# Sheet1.net
KiCad netlist of a schematic drawn in Altium Designer
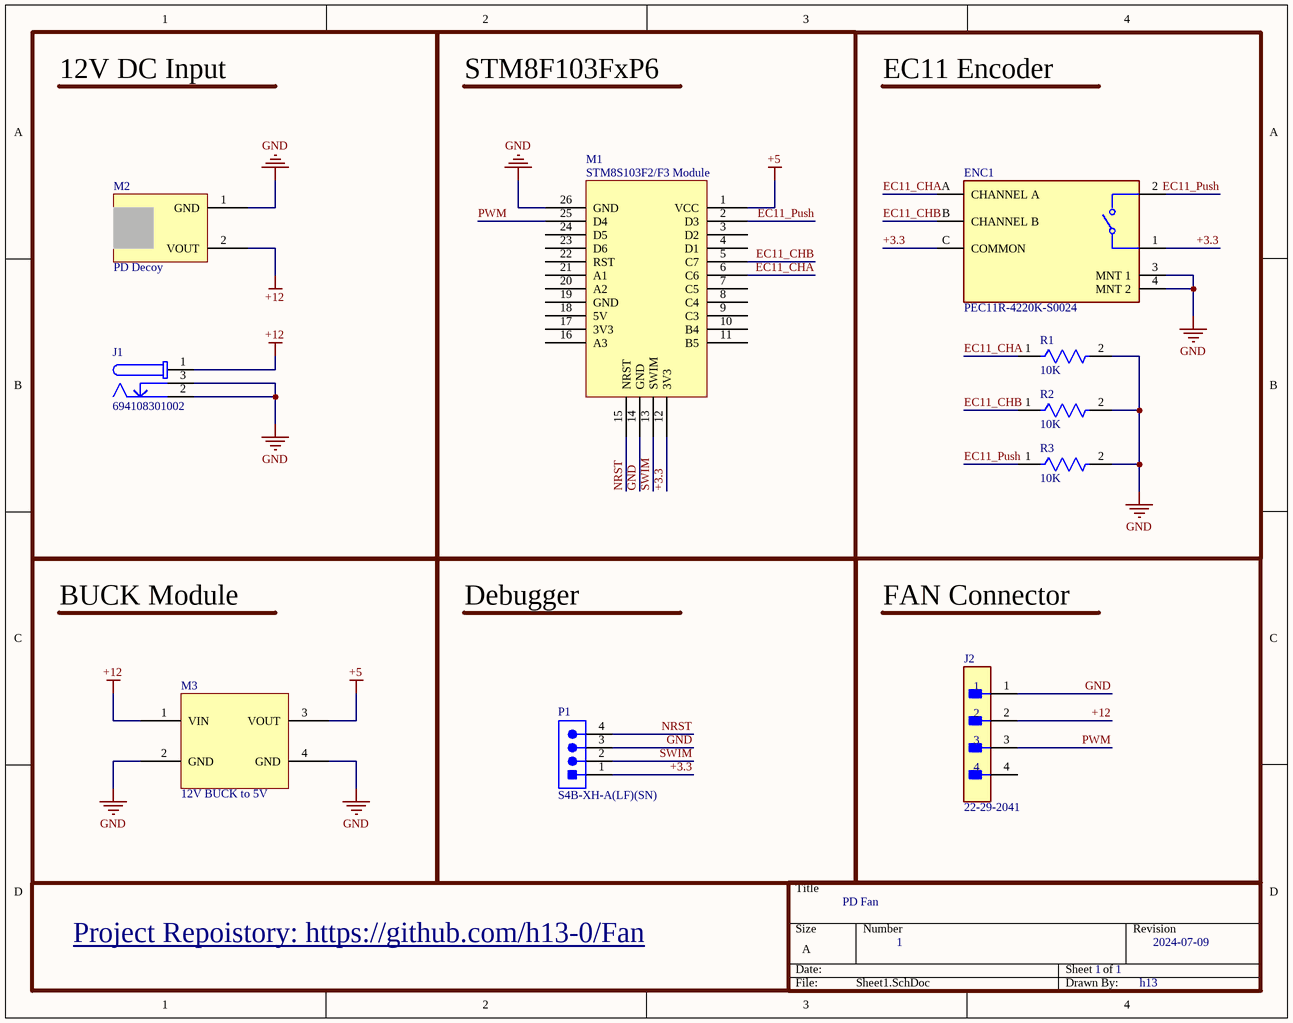
[diagram p0: Sheet1.SchDoc]

(export (version "E")
  (design (tool "Eeschema 10.0.6"))
  (components
    (comp (ref "ENC1")
      (value "PEC11R-4220K-S0024")
      (footprint "FP-PEC11R-4220K-S0024-MFG")
      (description "ROTARY ENCODER INCREMENTAL 24PPR")
      (libsource (lib "Altium Content Vault") (part "d75f9e24c474ed3fe2cf82f27e06f2a"))
    )
    (comp (ref "J1")
      (value "694108301002")
      (footprint "694108301002")
      (libsource (lib "Altium Content Vault") (part "DC Power Jack"))
    )
    (comp (ref "J2")
      (value "22-29-2041")
      (footprint "FP-22-29-2041-MFG")
      (description "CONN HEADER VERT 4POS 2.54MM")
      (libsource (lib "Altium Content Vault") (part "299a8cea1bdcbc3624fe62c390fa72c"))
    )
    (comp (ref "M1")
      (value "STM8S103F2/F3 Module")
      (libsource (lib "STM8S103F") (part "STM8S103F2/F3 Module"))
    )
    (comp (ref "M2") (value "PD Decoy") (libsource (lib "PD_Decoy") (part "PD Decoy")))
    (comp (ref "M3") (value "12V BUCK to 5V") (libsource (lib "BUCK_BOOST") (part "BUCK ¦ BOOST")))
    (comp (ref "P1")
      (value "S4B-XH-A(LF)(SN)")
      (footprint "JST-S4B-XH-A(LF)(SN)_V")
      (libsource (lib "Altium Content Vault") (part "CN-1P-M-R4"))
    )
    (comp (ref "R1")
      (value "10K")
      (footprint "FP-MRS25-MFG")
      (description "RES 1K OHM 0.6W 1% AXIAL")
      (fields (field (name "TOLERANCE") "1%"))
      (libsource (lib "Altium Content Vault") (part "1029c3af85768c4190bb7ad29bc67b5"))
    )
    (comp (ref "R2")
      (value "10K")
      (footprint "FP-MRS25-MFG")
      (description "RES 1K OHM 0.6W 1% AXIAL")
      (fields (field (name "TOLERANCE") "1%"))
      (libsource (lib "Altium Content Vault") (part "1029c3af85768c4190bb7ad29bc67b5"))
    )
    (comp (ref "R3")
      (value "10K")
      (footprint "FP-MRS25-MFG")
      (description "RES 1K OHM 0.6W 1% AXIAL")
      (fields (field (name "TOLERANCE") "1%"))
      (libsource (lib "Altium Content Vault") (part "1029c3af85768c4190bb7ad29bc67b5"))
    )
  )
  (nets
    (net (code "1") (name "+5") (class "Default")
      (node (ref "M1") (pin "1") (pinfunction "VCC_1") (pintype "passive"))
      (node (ref "M3") (pin "3") (pinfunction "VOUT_3") (pintype "passive"))
    )
    (net (code "2") (name "+12") (class "Default")
      (node (ref "J1") (pin "1") (pinfunction "1_1") (pintype "passive"))
      (node (ref "J2") (pin "2") (pinfunction "2_2") (pintype "passive"))
      (node (ref "M2") (pin "2") (pinfunction "VOUT_2") (pintype "passive"))
      (node (ref "M3") (pin "1") (pinfunction "VIN_1") (pintype "passive"))
    )
    (net (code "3") (name "/+3.3") (class "Default")
      (node (ref "ENC1") (pin "1") (pinfunction "1_1") (pintype "passive"))
      (node (ref "ENC1") (pin "C") (pinfunction "COMMON_C") (pintype "passive"))
      (node (ref "M1") (pin "12") (pinfunction "3V3_12") (pintype "passive"))
      (node (ref "P1") (pin "1") (pinfunction "1_1") (pintype "passive"))
    )
    (net (code "4") (name "/EC11_CHA") (class "Default")
      (node (ref "ENC1") (pin "A") (pinfunction "CHANNEL_A_A") (pintype "passive"))
      (node (ref "M1") (pin "6") (pinfunction "C6_6") (pintype "passive"))
      (node (ref "R1") (pin "1") (pinfunction "1_1") (pintype "passive"))
    )
    (net (code "5") (name "/EC11_CHB") (class "Default")
      (node (ref "ENC1") (pin "B") (pinfunction "CHANNEL_B_B") (pintype "passive"))
      (node (ref "M1") (pin "5") (pinfunction "C7_5") (pintype "passive"))
      (node (ref "R2") (pin "1") (pinfunction "1_1") (pintype "passive"))
    )
    (net (code "6") (name "/EC11_Push") (class "Default")
      (node (ref "ENC1") (pin "2") (pinfunction "2_2") (pintype "passive"))
      (node (ref "M1") (pin "2") (pinfunction "D3_2") (pintype "passive"))
      (node (ref "R3") (pin "1") (pinfunction "1_1") (pintype "passive"))
    )
    (net (code "7") (name "/NRST") (class "Default")
      (node (ref "M1") (pin "15") (pinfunction "NRST_15") (pintype "passive"))
      (node (ref "P1") (pin "4") (pinfunction "4_4") (pintype "passive"))
    )
    (net (code "8") (name "/PWM") (class "Default")
      (node (ref "J2") (pin "3") (pinfunction "3_3") (pintype "passive"))
      (node (ref "M1") (pin "25") (pinfunction "D4_25") (pintype "passive"))
    )
    (net (code "9") (name "/SWIM") (class "Default")
      (node (ref "M1") (pin "13") (pinfunction "SWIM_13") (pintype "passive"))
      (node (ref "P1") (pin "2") (pinfunction "2_2") (pintype "passive"))
    )
    (net (code "10") (name "GND") (class "Default")
      (node (ref "ENC1") (pin "3") (pinfunction "MNT_1_3") (pintype "passive"))
      (node (ref "ENC1") (pin "4") (pinfunction "MNT_2_4") (pintype "passive"))
      (node (ref "J1") (pin "2") (pinfunction "2_2") (pintype "passive"))
      (node (ref "J1") (pin "3") (pinfunction "3_3") (pintype "passive"))
      (node (ref "J2") (pin "1") (pinfunction "1_1") (pintype "passive"))
      (node (ref "M1") (pin "14") (pinfunction "GND_14") (pintype "passive"))
      (node (ref "M1") (pin "26") (pinfunction "GND_26") (pintype "passive"))
      (node (ref "M2") (pin "1") (pinfunction "GND_1") (pintype "passive"))
      (node (ref "M3") (pin "2") (pinfunction "GND_2") (pintype "passive"))
      (node (ref "M3") (pin "4") (pinfunction "GND_4") (pintype "passive"))
      (node (ref "P1") (pin "3") (pinfunction "3_3") (pintype "passive"))
      (node (ref "R1") (pin "2") (pinfunction "2_2") (pintype "passive"))
      (node (ref "R2") (pin "2") (pinfunction "2_2") (pintype "passive"))
      (node (ref "R3") (pin "2") (pinfunction "2_2") (pintype "passive"))
    )
    (net (code "11") (name "unconnected-(J2-Pad4)") (class "Default")
      (node (ref "J2") (pin "4") (pinfunction "4_4") (pintype "passive"))
    )
    (net (code "12") (name "unconnected-(M1-3V3-Pad17)") (class "Default")
      (node (ref "M1") (pin "17") (pinfunction "3V3_17") (pintype "passive"))
    )
    (net (code "13") (name "unconnected-(M1-5V-Pad18)") (class "Default")
      (node (ref "M1") (pin "18") (pinfunction "5V_18") (pintype "passive"))
    )
    (net (code "14") (name "unconnected-(M1-A1-Pad21)") (class "Default")
      (node (ref "M1") (pin "21") (pinfunction "A1_21") (pintype "passive"))
    )
    (net (code "15") (name "unconnected-(M1-A2-Pad20)") (class "Default")
      (node (ref "M1") (pin "20") (pinfunction "A2_20") (pintype "passive"))
    )
    (net (code "16") (name "unconnected-(M1-A3-Pad16)") (class "Default")
      (node (ref "M1") (pin "16") (pinfunction "A3_16") (pintype "passive"))
    )
    (net (code "17") (name "unconnected-(M1-B4-Pad10)") (class "Default")
      (node (ref "M1") (pin "10") (pinfunction "B4_10") (pintype "passive"))
    )
    (net (code "18") (name "unconnected-(M1-B5-Pad11)") (class "Default")
      (node (ref "M1") (pin "11") (pinfunction "B5_11") (pintype "passive"))
    )
    (net (code "19") (name "unconnected-(M1-C3-Pad9)") (class "Default")
      (node (ref "M1") (pin "9") (pinfunction "C3_9") (pintype "passive"))
    )
    (net (code "20") (name "unconnected-(M1-C4-Pad8)") (class "Default")
      (node (ref "M1") (pin "8") (pinfunction "C4_8") (pintype "passive"))
    )
    (net (code "21") (name "unconnected-(M1-C5-Pad7)") (class "Default")
      (node (ref "M1") (pin "7") (pinfunction "C5_7") (pintype "passive"))
    )
    (net (code "22") (name "unconnected-(M1-D1-Pad4)") (class "Default")
      (node (ref "M1") (pin "4") (pinfunction "D1_4") (pintype "passive"))
    )
    (net (code "23") (name "unconnected-(M1-D2-Pad3)") (class "Default")
      (node (ref "M1") (pin "3") (pinfunction "D2_3") (pintype "passive"))
    )
    (net (code "24") (name "unconnected-(M1-D5-Pad24)") (class "Default")
      (node (ref "M1") (pin "24") (pinfunction "D5_24") (pintype "passive"))
    )
    (net (code "25") (name "unconnected-(M1-D6-Pad23)") (class "Default")
      (node (ref "M1") (pin "23") (pinfunction "D6_23") (pintype "passive"))
    )
    (net (code "26") (name "unconnected-(M1-GND-Pad19)") (class "Default")
      (node (ref "M1") (pin "19") (pinfunction "GND_19") (pintype "passive"))
    )
    (net (code "27") (name "unconnected-(M1-RST-Pad22)") (class "Default")
      (node (ref "M1") (pin "22") (pinfunction "RST_22") (pintype "passive"))
    )
  )
)
